# akabeacon_mini.net
KiCad netlist of a schematic drawn in EAGLE
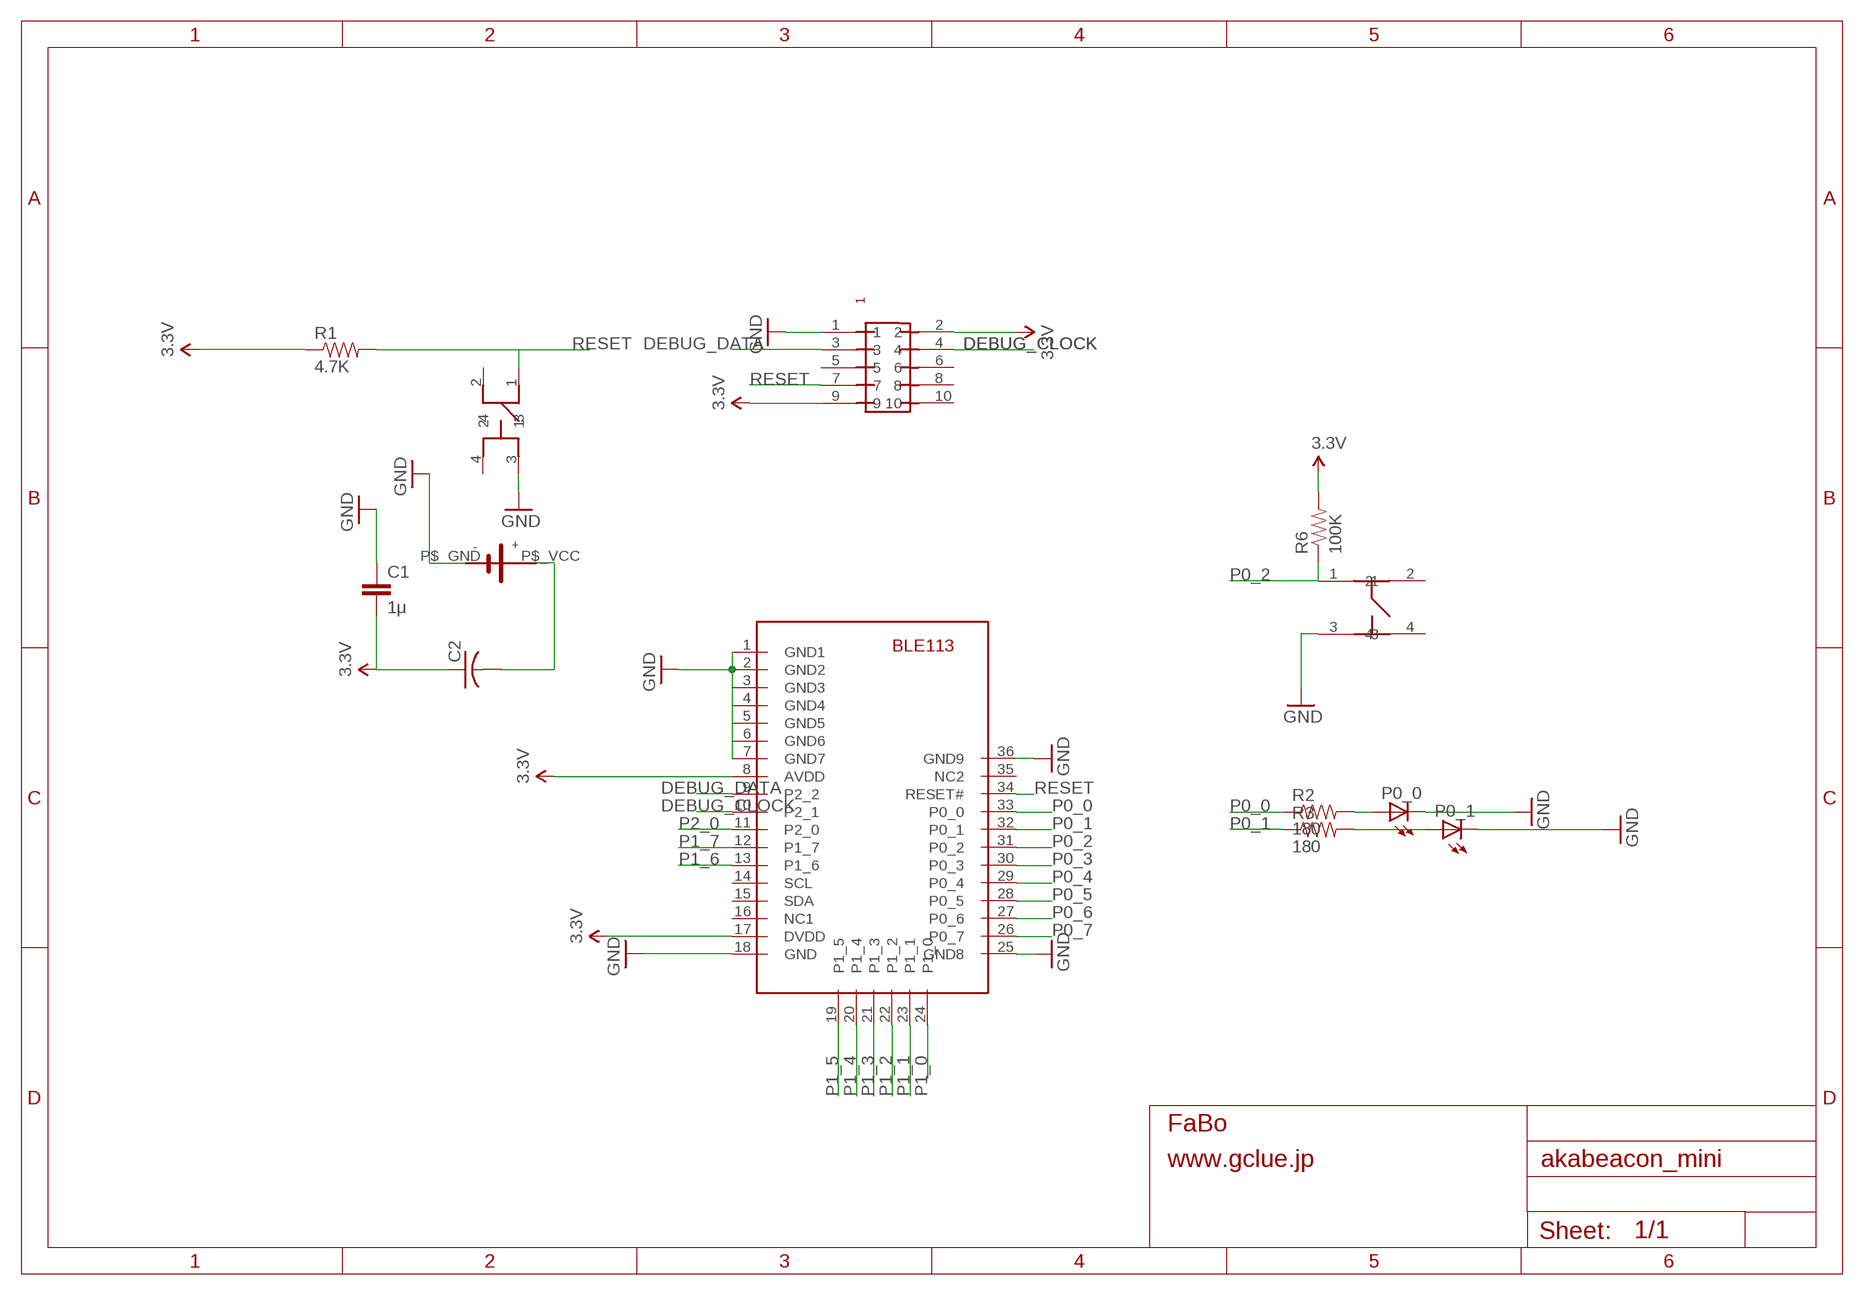
[diagram p0: schematic, sheet 1]

(export (version "E")
  (design (tool "Eeschema 10.0.6"))
  (components
    (comp (ref "C1")
      (value "1μ")
      (footprint "eagle-import:0603-CAP")
      (libsource (lib "eagle-import") (part "CAP0603-CAP"))
    )
    (comp (ref "C2")
      (value "C-USC3225")
      (footprint "eagle-import:C3225")
      (libsource (lib "eagle-import") (part "C-USC3225"))
    )
    (comp (ref "P0_0")
      (value "LEDCHIP-LED0603")
      (footprint "eagle-import:CHIP-LED0603")
      (libsource (lib "eagle-import") (part "LEDCHIP-LED0603"))
    )
    (comp (ref "P0_1")
      (value "LEDCHIP-LED0603")
      (footprint "eagle-import:CHIP-LED0603")
      (libsource (lib "eagle-import") (part "LEDCHIP-LED0603"))
    )
    (comp (ref "R1")
      (value "4.7K")
      (footprint "eagle-import:0603-RES")
      (libsource (lib "eagle-import") (part "RESISTOR0603-RES"))
    )
    (comp (ref "R2")
      (value "180")
      (footprint "eagle-import:0603-RES")
      (libsource (lib "eagle-import") (part "RESISTOR0603-RES"))
    )
    (comp (ref "R3")
      (value "180")
      (footprint "eagle-import:0603-RES")
      (libsource (lib "eagle-import") (part "RESISTOR0603-RES"))
    )
    (comp (ref "R6")
      (value "100K")
      (footprint "eagle-import:0603-RES")
      (libsource (lib "eagle-import") (part "RESISTOR0603-RES"))
    )
    (comp (ref "U$1")
      (value "SMTU2450-BOTTOM-MINI")
      (footprint "eagle-import:SMTU2450-BOTTOM-MINI")
      (libsource (lib "eagle-import") (part "SMTU2450-BOTTOM-MINI"))
    )
    (comp (ref "U$2")
      (value "SWITCH-LS6J2M-T")
      (footprint "eagle-import:SWICTH-LS6J2M-T")
      (libsource (lib "eagle-import") (part "SWITCH-LS6J2M-T"))
    )
    (comp (ref "U$3")
      (value "PIN-HEADER-SMT(1.27MM)2X5")
      (footprint "eagle-import:PIN-HEADER-SMT(1.27MM)2X5")
      (libsource (lib "eagle-import") (part "PIN-HEADER-SMT(1.27MM)2X5"))
    )
    (comp (ref "U$4")
      (value "BLE113")
      (footprint "eagle-import:BLE113")
      (libsource (lib "eagle-import") (part "BLE113"))
    )
    (comp (ref "U$5")
      (value "SWICTH-4P(KMR2)")
      (footprint "eagle-import:SWITCH-4P(KMR2)")
      (libsource (lib "eagle-import") (part "SWICTH-4P(KMR2)"))
    )
  )
  (nets
    (net (code "1") (name "/DEBUG_CLOCK") (class "Default")
      (node (ref "U$3") (pin "4") (pinfunction "4_4") (pintype "bidirectional"))
      (node (ref "U$4") (pin "10") (pinfunction "P2_1_10") (pintype "bidirectional"))
    )
    (net (code "2") (name "/DEBUG_DATA") (class "Default")
      (node (ref "U$3") (pin "3") (pinfunction "3_3") (pintype "bidirectional"))
      (node (ref "U$4") (pin "9") (pinfunction "P2_2_9") (pintype "bidirectional"))
    )
    (net (code "3") (name "/P0_0") (class "Default")
      (node (ref "R2") (pin "1") (pinfunction "1_1") (pintype "passive"))
      (node (ref "U$4") (pin "33") (pinfunction "P0_0_33") (pintype "bidirectional"))
    )
    (net (code "4") (name "/P0_1") (class "Default")
      (node (ref "R3") (pin "1") (pinfunction "1_1") (pintype "passive"))
      (node (ref "U$4") (pin "32") (pinfunction "P0_1_32") (pintype "bidirectional"))
    )
    (net (code "5") (name "/P0_2") (class "Default")
      (node (ref "R6") (pin "1") (pinfunction "1_1") (pintype "passive"))
      (node (ref "U$4") (pin "31") (pinfunction "P0_2_31") (pintype "bidirectional"))
      (node (ref "U$5") (pin "1") (pinfunction "1_1") (pintype "bidirectional"))
    )
    (net (code "6") (name "/P0_3") (class "Default")
      (node (ref "U$4") (pin "30") (pinfunction "P0_3_30") (pintype "bidirectional"))
    )
    (net (code "7") (name "/P0_4") (class "Default")
      (node (ref "U$4") (pin "29") (pinfunction "P0_4_29") (pintype "bidirectional"))
    )
    (net (code "8") (name "/P0_5") (class "Default")
      (node (ref "U$4") (pin "28") (pinfunction "P0_5_28") (pintype "bidirectional"))
    )
    (net (code "9") (name "/P0_6") (class "Default")
      (node (ref "U$4") (pin "27") (pinfunction "P0_6_27") (pintype "bidirectional"))
    )
    (net (code "10") (name "/P0_7") (class "Default")
      (node (ref "U$4") (pin "26") (pinfunction "P0_7_26") (pintype "bidirectional"))
    )
    (net (code "11") (name "/P1_0") (class "Default")
      (node (ref "U$4") (pin "24") (pinfunction "P1_0_24") (pintype "bidirectional"))
    )
    (net (code "12") (name "/P1_1") (class "Default")
      (node (ref "U$4") (pin "23") (pinfunction "P1_1_23") (pintype "bidirectional"))
    )
    (net (code "13") (name "/P1_2") (class "Default")
      (node (ref "U$4") (pin "22") (pinfunction "P1_2_22") (pintype "bidirectional"))
    )
    (net (code "14") (name "/P1_3") (class "Default")
      (node (ref "U$4") (pin "21") (pinfunction "P1_3_21") (pintype "bidirectional"))
    )
    (net (code "15") (name "/P1_4") (class "Default")
      (node (ref "U$4") (pin "20") (pinfunction "P1_4_20") (pintype "bidirectional"))
    )
    (net (code "16") (name "/P1_5") (class "Default")
      (node (ref "U$4") (pin "19") (pinfunction "P1_5_19") (pintype "bidirectional"))
    )
    (net (code "17") (name "/P1_6") (class "Default")
      (node (ref "U$4") (pin "13") (pinfunction "P1_6_13") (pintype "bidirectional"))
    )
    (net (code "18") (name "/P1_7") (class "Default")
      (node (ref "U$4") (pin "12") (pinfunction "P1_7_12") (pintype "bidirectional"))
    )
    (net (code "19") (name "/P2_0") (class "Default")
      (node (ref "U$4") (pin "11") (pinfunction "P2_0_11") (pintype "bidirectional"))
    )
    (net (code "20") (name "/RESET") (class "Default")
      (node (ref "R1") (pin "2") (pinfunction "2_2") (pintype "passive"))
      (node (ref "U$2") (pin "1") (pinfunction "1_1") (pintype "bidirectional"))
      (node (ref "U$3") (pin "7") (pinfunction "7_7") (pintype "bidirectional"))
      (node (ref "U$4") (pin "34") (pinfunction "RESET#_34") (pintype "bidirectional"))
    )
    (net (code "21") (name "3.3V") (class "Default")
      (node (ref "C1") (pin "2") (pinfunction "2_2") (pintype "passive"))
      (node (ref "C2") (pin "1") (pinfunction "1_1") (pintype "passive"))
      (node (ref "R1") (pin "1") (pinfunction "1_1") (pintype "passive"))
      (node (ref "R6") (pin "2") (pinfunction "2_2") (pintype "passive"))
      (node (ref "U$3") (pin "2") (pinfunction "2_2") (pintype "bidirectional"))
      (node (ref "U$3") (pin "9") (pinfunction "9_9") (pintype "bidirectional"))
      (node (ref "U$4") (pin "17") (pinfunction "DVDD_17") (pintype "bidirectional"))
      (node (ref "U$4") (pin "8") (pinfunction "AVDD_8") (pintype "bidirectional"))
    )
    (net (code "22") (name "GND") (class "Default")
      (node (ref "C1") (pin "1") (pinfunction "1_1") (pintype "passive"))
      (node (ref "P0_0") (pin "C") (pinfunction "C_C") (pintype "passive"))
      (node (ref "P0_1") (pin "C") (pinfunction "C_C") (pintype "passive"))
      (node (ref "U$1") (pin "P$_GND") (pinfunction "P$_GND_P$_GND") (pintype "bidirectional"))
      (node (ref "U$2") (pin "3") (pinfunction "3_3") (pintype "bidirectional"))
      (node (ref "U$3") (pin "1") (pinfunction "1_1") (pintype "bidirectional"))
      (node (ref "U$4") (pin "1") (pinfunction "GND1_1") (pintype "bidirectional"))
      (node (ref "U$4") (pin "18") (pinfunction "GND_18") (pintype "bidirectional"))
      (node (ref "U$4") (pin "2") (pinfunction "GND2_2") (pintype "bidirectional"))
      (node (ref "U$4") (pin "25") (pinfunction "GND8_25") (pintype "bidirectional"))
      (node (ref "U$4") (pin "3") (pinfunction "GND3_3") (pintype "bidirectional"))
      (node (ref "U$4") (pin "36") (pinfunction "GND9_36") (pintype "bidirectional"))
      (node (ref "U$4") (pin "4") (pinfunction "GND4_4") (pintype "bidirectional"))
      (node (ref "U$4") (pin "5") (pinfunction "GND5_5") (pintype "bidirectional"))
      (node (ref "U$4") (pin "6") (pinfunction "GND6_6") (pintype "bidirectional"))
      (node (ref "U$4") (pin "7") (pinfunction "GND7_7") (pintype "bidirectional"))
      (node (ref "U$5") (pin "3") (pinfunction "3_3") (pintype "bidirectional"))
    )
    (net (code "23") (name "Net-(C2-Pad2)") (class "Default")
      (node (ref "C2") (pin "2") (pinfunction "2_2") (pintype "passive"))
      (node (ref "U$1") (pin "P$_VCC") (pinfunction "P$_VCC_P$_VCC") (pintype "bidirectional"))
    )
    (net (code "24") (name "Net-(P0_0-PadA)") (class "Default")
      (node (ref "P0_0") (pin "A") (pinfunction "A_A") (pintype "passive"))
      (node (ref "R2") (pin "2") (pinfunction "2_2") (pintype "passive"))
    )
    (net (code "25") (name "Net-(P0_1-PadA)") (class "Default")
      (node (ref "P0_1") (pin "A") (pinfunction "A_A") (pintype "passive"))
      (node (ref "R3") (pin "2") (pinfunction "2_2") (pintype "passive"))
    )
    (net (code "26") (name "unconnected-(U$2-Pad2)") (class "Default")
      (node (ref "U$2") (pin "2") (pinfunction "2_2") (pintype "bidirectional"))
    )
    (net (code "27") (name "unconnected-(U$2-Pad4)") (class "Default")
      (node (ref "U$2") (pin "4") (pinfunction "4_4") (pintype "bidirectional"))
    )
    (net (code "28") (name "unconnected-(U$3-Pad5)") (class "Default")
      (node (ref "U$3") (pin "5") (pinfunction "5_5") (pintype "bidirectional"))
    )
    (net (code "29") (name "unconnected-(U$3-Pad6)") (class "Default")
      (node (ref "U$3") (pin "6") (pinfunction "6_6") (pintype "bidirectional"))
    )
    (net (code "30") (name "unconnected-(U$3-Pad8)") (class "Default")
      (node (ref "U$3") (pin "8") (pinfunction "8_8") (pintype "bidirectional"))
    )
    (net (code "31") (name "unconnected-(U$3-Pad10)") (class "Default")
      (node (ref "U$3") (pin "10") (pinfunction "10_10") (pintype "bidirectional"))
    )
    (net (code "32") (name "unconnected-(U$4-NC1-Pad16)") (class "Default")
      (node (ref "U$4") (pin "16") (pinfunction "NC1_16") (pintype "bidirectional"))
    )
    (net (code "33") (name "unconnected-(U$4-NC2-Pad35)") (class "Default")
      (node (ref "U$4") (pin "35") (pinfunction "NC2_35") (pintype "bidirectional"))
    )
    (net (code "34") (name "unconnected-(U$4-SCL-Pad14)") (class "Default")
      (node (ref "U$4") (pin "14") (pinfunction "SCL_14") (pintype "bidirectional"))
    )
    (net (code "35") (name "unconnected-(U$4-SDA-Pad15)") (class "Default")
      (node (ref "U$4") (pin "15") (pinfunction "SDA_15") (pintype "bidirectional"))
    )
    (net (code "36") (name "unconnected-(U$5-Pad2)") (class "Default")
      (node (ref "U$5") (pin "2") (pinfunction "2_2") (pintype "bidirectional"))
    )
    (net (code "37") (name "unconnected-(U$5-Pad4)") (class "Default")
      (node (ref "U$5") (pin "4") (pinfunction "4_4") (pintype "bidirectional"))
    )
  )
)
